# Projeto_esquem_tico_NOVO.net
KiCad netlist of a schematic drawn in EAGLE
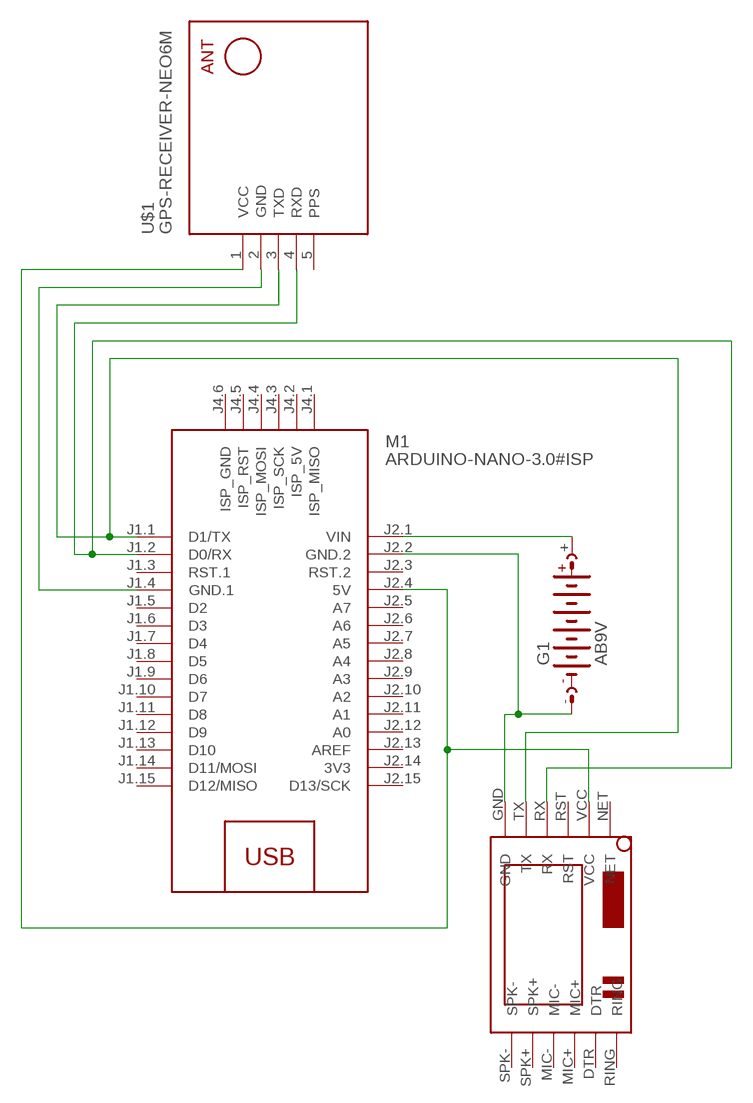
[diagram p0: schematic, sheet 1]

(export (version "E")
  (design (tool "Eeschema 10.0.6"))
  (components
    (comp (ref "G1")
      (value "AB9V")
      (footprint "eagle-import:AB9V")
      (libsource (lib "eagle-import") (part "AB9V"))
    )
    (comp (ref "M1")
      (value "ARDUINO-NANO-3.0#ISP")
      (footprint "eagle-import:ARDUINO-NANO-3.0#ISP")
      (libsource (lib "eagle-import") (part "ARDUINO-NANO-3.0#ISP"))
    )
    (comp (ref "U$1")
      (value "GPS-RECEIVER-NEO6M")
      (footprint "eagle-import:GPS-RECEIVER-NEO6M")
      (libsource (lib "eagle-import") (part "GPS-RECEIVER-NEO6M"))
    )
    (comp (ref "U$2")
      (value "SIM800LMODULE")
      (footprint "eagle-import:SIM800LMODULE")
      (libsource (lib "eagle-import") (part "SIM800LMODULE"))
    )
  )
  (nets
    (net (code "1") (name "/3V3") (class "Default")
      (node (ref "M1") (pin "J2.14") (pinfunction "3V3_J2.14") (pintype "power_in"))
    )
    (net (code "2") (name "/PPS") (class "Default")
      (node (ref "U$1") (pin "5") (pinfunction "PPS_5") (pintype "power_in"))
    )
    (net (code "3") (name "Net-(M1-5V)") (class "Default")
      (node (ref "M1") (pin "J2.4") (pinfunction "5V_J2.4") (pintype "power_in"))
      (node (ref "U$1") (pin "1") (pinfunction "VCC_1") (pintype "bidirectional"))
      (node (ref "U$2") (pin "VCC") (pinfunction "VCC_VCC") (pintype "bidirectional"))
    )
    (net (code "4") (name "Net-(M1-D0{slash}RX)") (class "Default")
      (node (ref "M1") (pin "J1.2") (pinfunction "D0/RX_J1.2") (pintype "bidirectional"))
      (node (ref "U$1") (pin "4") (pinfunction "RXD_4") (pintype "power_in"))
      (node (ref "U$2") (pin "RX") (pinfunction "RX_RX") (pintype "bidirectional"))
    )
    (net (code "5") (name "Net-(M1-D1{slash}TX)") (class "Default")
      (node (ref "M1") (pin "J1.1") (pinfunction "D1/TX_J1.1") (pintype "bidirectional"))
      (node (ref "U$1") (pin "3") (pinfunction "TXD_3") (pintype "bidirectional"))
      (node (ref "U$2") (pin "TX") (pinfunction "TX_TX") (pintype "bidirectional"))
    )
    (net (code "6") (name "Net-(M1-GND.1)") (class "Default")
      (node (ref "M1") (pin "J1.4") (pinfunction "GND.1_J1.4") (pintype "power_in"))
      (node (ref "U$1") (pin "2") (pinfunction "GND_2") (pintype "bidirectional"))
    )
    (net (code "7") (name "Net-(M1-GND.2)") (class "Default")
      (node (ref "G1") (pin "-") (pinfunction "-_-") (pintype "passive"))
      (node (ref "M1") (pin "J2.2") (pinfunction "GND.2_J2.2") (pintype "power_in"))
      (node (ref "U$2") (pin "GND") (pinfunction "GND_GND") (pintype "bidirectional"))
    )
    (net (code "8") (name "Net-(M1-VIN)") (class "Default")
      (node (ref "G1") (pin "+") (pinfunction "+_+") (pintype "passive"))
      (node (ref "M1") (pin "J2.1") (pinfunction "VIN_J2.1") (pintype "power_in"))
    )
    (net (code "9") (name "unconnected-(M1-A0-PadJ2.12)") (class "Default")
      (node (ref "M1") (pin "J2.12") (pinfunction "A0_J2.12") (pintype "bidirectional"))
    )
    (net (code "10") (name "unconnected-(M1-A1-PadJ2.11)") (class "Default")
      (node (ref "M1") (pin "J2.11") (pinfunction "A1_J2.11") (pintype "bidirectional"))
    )
    (net (code "11") (name "unconnected-(M1-A2-PadJ2.10)") (class "Default")
      (node (ref "M1") (pin "J2.10") (pinfunction "A2_J2.10") (pintype "bidirectional"))
    )
    (net (code "12") (name "unconnected-(M1-A3-PadJ2.9)") (class "Default")
      (node (ref "M1") (pin "J2.9") (pinfunction "A3_J2.9") (pintype "bidirectional"))
    )
    (net (code "13") (name "unconnected-(M1-A4-PadJ2.8)") (class "Default")
      (node (ref "M1") (pin "J2.8") (pinfunction "A4_J2.8") (pintype "bidirectional"))
    )
    (net (code "14") (name "unconnected-(M1-A5-PadJ2.7)") (class "Default")
      (node (ref "M1") (pin "J2.7") (pinfunction "A5_J2.7") (pintype "bidirectional"))
    )
    (net (code "15") (name "unconnected-(M1-A6-PadJ2.6)") (class "Default")
      (node (ref "M1") (pin "J2.6") (pinfunction "A6_J2.6") (pintype "bidirectional"))
    )
    (net (code "16") (name "unconnected-(M1-A7-PadJ2.5)") (class "Default")
      (node (ref "M1") (pin "J2.5") (pinfunction "A7_J2.5") (pintype "bidirectional"))
    )
    (net (code "17") (name "unconnected-(M1-AREF-PadJ2.13)") (class "Default")
      (node (ref "M1") (pin "J2.13") (pinfunction "AREF_J2.13") (pintype "bidirectional"))
    )
    (net (code "18") (name "unconnected-(M1-D2-PadJ1.5)") (class "Default")
      (node (ref "M1") (pin "J1.5") (pinfunction "D2_J1.5") (pintype "bidirectional"))
    )
    (net (code "19") (name "unconnected-(M1-D3-PadJ1.6)") (class "Default")
      (node (ref "M1") (pin "J1.6") (pinfunction "D3_J1.6") (pintype "bidirectional"))
    )
    (net (code "20") (name "unconnected-(M1-D4-PadJ1.7)") (class "Default")
      (node (ref "M1") (pin "J1.7") (pinfunction "D4_J1.7") (pintype "bidirectional"))
    )
    (net (code "21") (name "unconnected-(M1-D5-PadJ1.8)") (class "Default")
      (node (ref "M1") (pin "J1.8") (pinfunction "D5_J1.8") (pintype "bidirectional"))
    )
    (net (code "22") (name "unconnected-(M1-D6-PadJ1.9)") (class "Default")
      (node (ref "M1") (pin "J1.9") (pinfunction "D6_J1.9") (pintype "bidirectional"))
    )
    (net (code "23") (name "unconnected-(M1-D7-PadJ1.10)") (class "Default")
      (node (ref "M1") (pin "J1.10") (pinfunction "D7_J1.10") (pintype "bidirectional"))
    )
    (net (code "24") (name "unconnected-(M1-D8-PadJ1.11)") (class "Default")
      (node (ref "M1") (pin "J1.11") (pinfunction "D8_J1.11") (pintype "bidirectional"))
    )
    (net (code "25") (name "unconnected-(M1-D9-PadJ1.12)") (class "Default")
      (node (ref "M1") (pin "J1.12") (pinfunction "D9_J1.12") (pintype "bidirectional"))
    )
    (net (code "26") (name "unconnected-(M1-D10-PadJ1.13)") (class "Default")
      (node (ref "M1") (pin "J1.13") (pinfunction "D10_J1.13") (pintype "bidirectional"))
    )
    (net (code "27") (name "unconnected-(M1-D11{slash}MOSI-PadJ1.14)") (class "Default")
      (node (ref "M1") (pin "J1.14") (pinfunction "D11/MOSI_J1.14") (pintype "bidirectional"))
    )
    (net (code "28") (name "unconnected-(M1-D12{slash}MISO-PadJ1.15)") (class "Default")
      (node (ref "M1") (pin "J1.15") (pinfunction "D12/MISO_J1.15") (pintype "bidirectional"))
    )
    (net (code "29") (name "unconnected-(M1-D13{slash}SCK-PadJ2.15)") (class "Default")
      (node (ref "M1") (pin "J2.15") (pinfunction "D13/SCK_J2.15") (pintype "bidirectional"))
    )
    (net (code "30") (name "unconnected-(M1-ISP_5V-PadJ4.2)") (class "Default")
      (node (ref "M1") (pin "J4.2") (pinfunction "ISP_5V_J4.2") (pintype "bidirectional"))
    )
    (net (code "31") (name "unconnected-(M1-ISP_GND-PadJ4.6)") (class "Default")
      (node (ref "M1") (pin "J4.6") (pinfunction "ISP_GND_J4.6") (pintype "bidirectional"))
    )
    (net (code "32") (name "unconnected-(M1-ISP_MISO-PadJ4.1)") (class "Default")
      (node (ref "M1") (pin "J4.1") (pinfunction "ISP_MISO_J4.1") (pintype "bidirectional"))
    )
    (net (code "33") (name "unconnected-(M1-ISP_MOSI-PadJ4.4)") (class "Default")
      (node (ref "M1") (pin "J4.4") (pinfunction "ISP_MOSI_J4.4") (pintype "bidirectional"))
    )
    (net (code "34") (name "unconnected-(M1-ISP_RST-PadJ4.5)") (class "Default")
      (node (ref "M1") (pin "J4.5") (pinfunction "ISP_RST_J4.5") (pintype "bidirectional"))
    )
    (net (code "35") (name "unconnected-(M1-ISP_SCK-PadJ4.3)") (class "Default")
      (node (ref "M1") (pin "J4.3") (pinfunction "ISP_SCK_J4.3") (pintype "bidirectional"))
    )
    (net (code "36") (name "unconnected-(M1-RST.1-PadJ1.3)") (class "Default")
      (node (ref "M1") (pin "J1.3") (pinfunction "RST.1_J1.3") (pintype "bidirectional"))
    )
    (net (code "37") (name "unconnected-(M1-RST.2-PadJ2.3)") (class "Default")
      (node (ref "M1") (pin "J2.3") (pinfunction "RST.2_J2.3") (pintype "bidirectional"))
    )
    (net (code "38") (name "unconnected-(U$2-PadDTR)") (class "Default")
      (node (ref "U$2") (pin "DTR") (pinfunction "DTR_DTR") (pintype "bidirectional"))
    )
    (net (code "39") (name "unconnected-(U$2-PadMIC+)") (class "Default")
      (node (ref "U$2") (pin "MIC+") (pinfunction "MIC+_MIC+") (pintype "bidirectional"))
    )
    (net (code "40") (name "unconnected-(U$2-PadMIC-)") (class "Default")
      (node (ref "U$2") (pin "MIC-") (pinfunction "MIC-_MIC-") (pintype "bidirectional"))
    )
    (net (code "41") (name "unconnected-(U$2-PadNET)") (class "Default")
      (node (ref "U$2") (pin "NET") (pinfunction "NET_NET") (pintype "bidirectional"))
    )
    (net (code "42") (name "unconnected-(U$2-PadRING)") (class "Default")
      (node (ref "U$2") (pin "RING") (pinfunction "RING_RING") (pintype "bidirectional"))
    )
    (net (code "43") (name "unconnected-(U$2-PadRST)") (class "Default")
      (node (ref "U$2") (pin "RST") (pinfunction "RST_RST") (pintype "bidirectional"))
    )
    (net (code "44") (name "unconnected-(U$2-PadSPK+)") (class "Default")
      (node (ref "U$2") (pin "SPK+") (pinfunction "SPK+_SPK+") (pintype "bidirectional"))
    )
    (net (code "45") (name "unconnected-(U$2-PadSPK-)") (class "Default")
      (node (ref "U$2") (pin "SPK-") (pinfunction "SPK-_SPK-") (pintype "bidirectional"))
    )
  )
)
